# 4channelsRelaySwitchv2.net
KiCad netlist of a schematic drawn in EAGLE
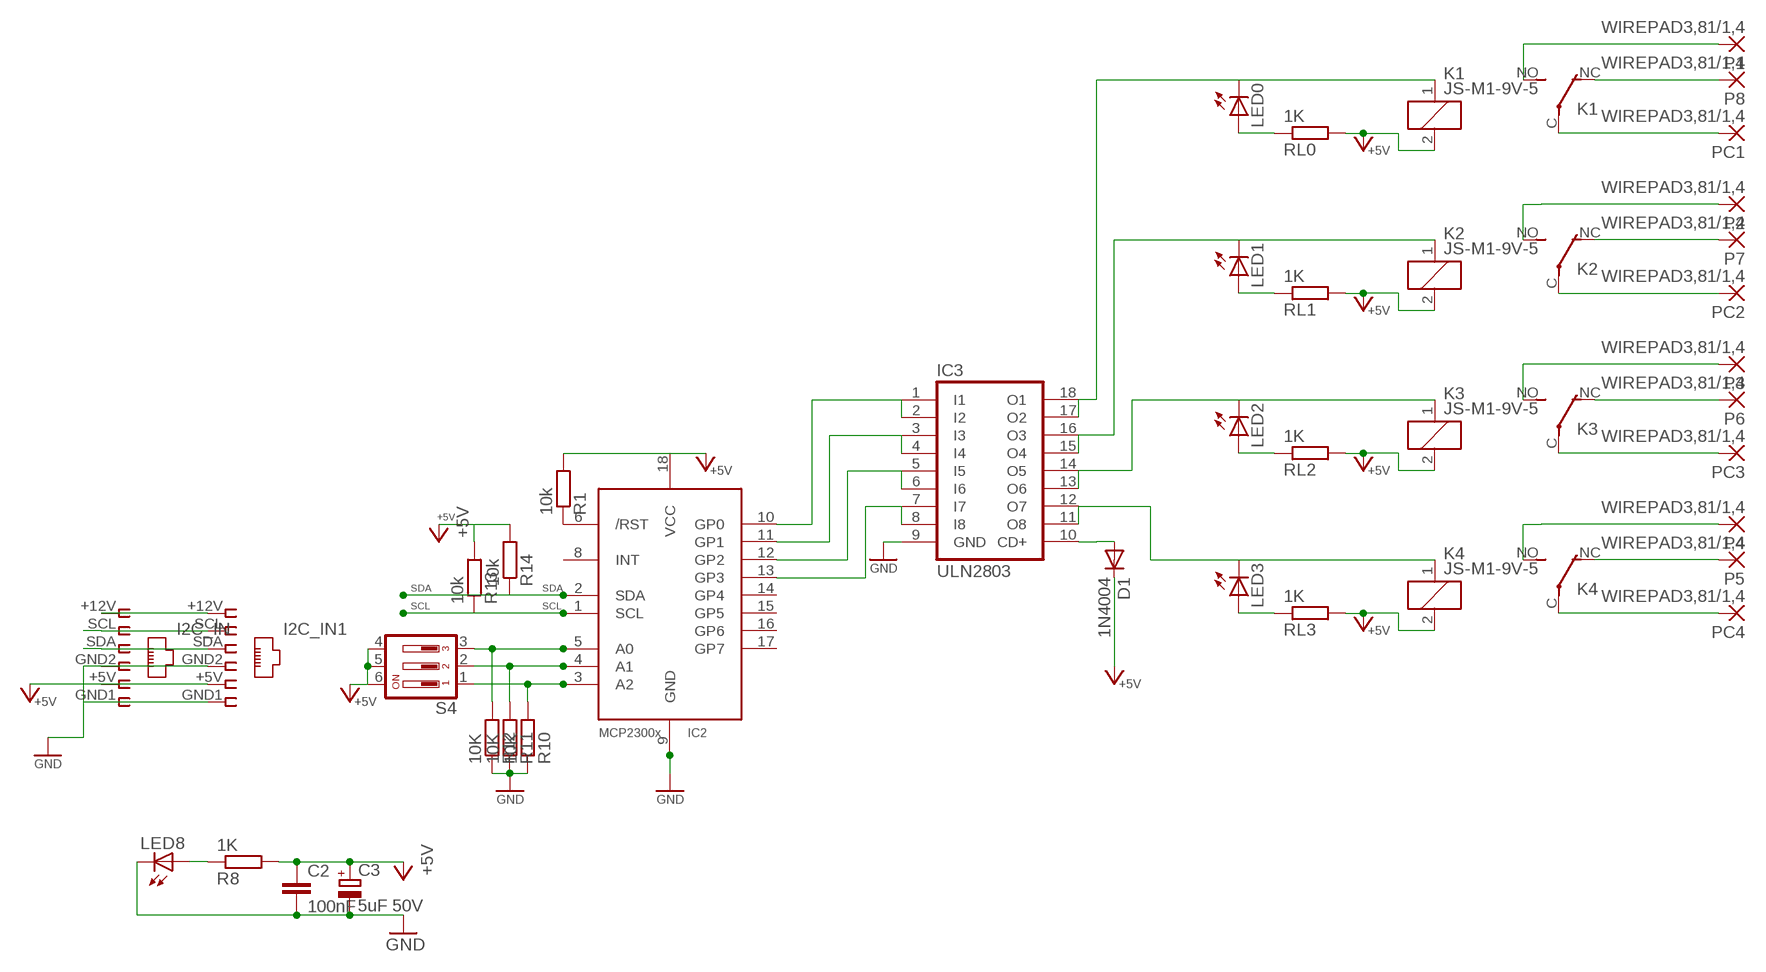
[diagram p0: schematic, sheet 1]

(export (version "E")
  (design (tool "Eeschema 10.0.6"))
  (components
    (comp (ref "C2")
      (value "100nF")
      (footprint "eagle-import:C1206")
      (libsource (lib "eagle-import") (part "C-EUC1206"))
    )
    (comp (ref "C3")
      (value "5uF 50V")
      (footprint "eagle-import:E3,5-8")
      (libsource (lib "eagle-import") (part "CPOL-EUE3.5-8"))
    )
    (comp (ref "D1")
      (value "1N4004")
      (footprint "eagle-import:DO41-10")
      (libsource (lib "eagle-import") (part "1N4004"))
    )
    (comp (ref "I2C_IN")
      (value "I2C 1")
      (footprint "eagle-import:RJ12-STRAIGHT-I2C")
      (libsource (lib "eagle-import") (part "RJ12STRAIGHT-I2C"))
    )
    (comp (ref "I2C_IN1")
      (value "I2C 2")
      (footprint "eagle-import:RJ12-STRAIGHT-I2C")
      (libsource (lib "eagle-import") (part "RJ12STRAIGHT-I2C"))
    )
    (comp (ref "IC2")
      (value "MCP2300X/P")
      (footprint "eagle-import:DIL18")
      (libsource (lib "eagle-import") (part "MCP2300X/P"))
    )
    (comp (ref "IC3")
      (value "ULN2803")
      (footprint "eagle-import:DIL18")
      (libsource (lib "eagle-import") (part "ULN2803A"))
    )
    (comp (ref "K1")
      (value "JS-M1-9V-5")
      (footprint "eagle-import:JS-M")
      (libsource (lib "eagle-import") (part "JS-M1-9V-5"))
    )
    (comp (ref "K2")
      (value "JS-M1-9V-5")
      (footprint "eagle-import:JS-M")
      (libsource (lib "eagle-import") (part "JS-M1-9V-5"))
    )
    (comp (ref "K3")
      (value "JS-M1-9V-5")
      (footprint "eagle-import:JS-M")
      (libsource (lib "eagle-import") (part "JS-M1-9V-5"))
    )
    (comp (ref "K4")
      (value "JS-M1-9V-5")
      (footprint "eagle-import:JS-M")
      (libsource (lib "eagle-import") (part "JS-M1-9V-5"))
    )
    (comp (ref "LED0")
      (value "LED3MM")
      (footprint "eagle-import:LED3MM")
      (libsource (lib "eagle-import") (part "LED3MM"))
    )
    (comp (ref "LED1")
      (value "LED3MM")
      (footprint "eagle-import:LED3MM")
      (libsource (lib "eagle-import") (part "LED3MM"))
    )
    (comp (ref "LED2")
      (value "LED3MM")
      (footprint "eagle-import:LED3MM")
      (libsource (lib "eagle-import") (part "LED3MM"))
    )
    (comp (ref "LED3")
      (value "LED3MM")
      (footprint "eagle-import:LED3MM")
      (libsource (lib "eagle-import") (part "LED3MM"))
    )
    (comp (ref "LED8")
      (value "LED3MM")
      (footprint "eagle-import:LED3MM")
      (libsource (lib "eagle-import") (part "LED3MM"))
    )
    (comp (ref "P1")
      (value "WIREPAD3,81/1,4")
      (footprint "eagle-import:3,81_1,4")
      (libsource (lib "eagle-import") (part "WIREPAD3,81/1,4"))
    )
    (comp (ref "P2")
      (value "WIREPAD3,81/1,4")
      (footprint "eagle-import:3,81_1,4")
      (libsource (lib "eagle-import") (part "WIREPAD3,81/1,4"))
    )
    (comp (ref "P3")
      (value "WIREPAD3,81/1,4")
      (footprint "eagle-import:3,81_1,4")
      (libsource (lib "eagle-import") (part "WIREPAD3,81/1,4"))
    )
    (comp (ref "P4")
      (value "WIREPAD3,81/1,4")
      (footprint "eagle-import:3,81_1,4")
      (libsource (lib "eagle-import") (part "WIREPAD3,81/1,4"))
    )
    (comp (ref "P5")
      (value "WIREPAD3,81/1,4")
      (footprint "eagle-import:3,81_1,4")
      (libsource (lib "eagle-import") (part "WIREPAD3,81/1,4"))
    )
    (comp (ref "P6")
      (value "WIREPAD3,81/1,4")
      (footprint "eagle-import:3,81_1,4")
      (libsource (lib "eagle-import") (part "WIREPAD3,81/1,4"))
    )
    (comp (ref "P7")
      (value "WIREPAD3,81/1,4")
      (footprint "eagle-import:3,81_1,4")
      (libsource (lib "eagle-import") (part "WIREPAD3,81/1,4"))
    )
    (comp (ref "P8")
      (value "WIREPAD3,81/1,4")
      (footprint "eagle-import:3,81_1,4")
      (libsource (lib "eagle-import") (part "WIREPAD3,81/1,4"))
    )
    (comp (ref "PC1")
      (value "WIREPAD3,81/1,4")
      (footprint "eagle-import:3,81_1,4")
      (libsource (lib "eagle-import") (part "WIREPAD3,81/1,4"))
    )
    (comp (ref "PC2")
      (value "WIREPAD3,81/1,4")
      (footprint "eagle-import:3,81_1,4")
      (libsource (lib "eagle-import") (part "WIREPAD3,81/1,4"))
    )
    (comp (ref "PC3")
      (value "WIREPAD3,81/1,4")
      (footprint "eagle-import:3,81_1,4")
      (libsource (lib "eagle-import") (part "WIREPAD3,81/1,4"))
    )
    (comp (ref "PC4")
      (value "WIREPAD3,81/1,4")
      (footprint "eagle-import:3,81_1,4")
      (libsource (lib "eagle-import") (part "WIREPAD3,81/1,4"))
    )
    (comp (ref "R1")
      (value "10k")
      (footprint "eagle-import:M1206")
      (libsource (lib "eagle-import") (part "R-EU_M1206"))
    )
    (comp (ref "R8")
      (value "1K")
      (footprint "eagle-import:M1206")
      (libsource (lib "eagle-import") (part "R-EU_M1206"))
    )
    (comp (ref "R10")
      (value "10K")
      (footprint "eagle-import:M1206")
      (libsource (lib "eagle-import") (part "R-EU_M1206"))
    )
    (comp (ref "R11")
      (value "10K")
      (footprint "eagle-import:M1206")
      (libsource (lib "eagle-import") (part "R-EU_M1206"))
    )
    (comp (ref "R12")
      (value "10K")
      (footprint "eagle-import:M1206")
      (libsource (lib "eagle-import") (part "R-EU_M1206"))
    )
    (comp (ref "R13")
      (value "10k")
      (footprint "eagle-import:M1206")
      (libsource (lib "eagle-import") (part "R-EU_M1206"))
    )
    (comp (ref "R14")
      (value "10k")
      (footprint "eagle-import:M1206")
      (libsource (lib "eagle-import") (part "R-EU_M1206"))
    )
    (comp (ref "RL0")
      (value "1K")
      (footprint "eagle-import:M1206")
      (libsource (lib "eagle-import") (part "R-EU_M1206"))
    )
    (comp (ref "RL1")
      (value "1K")
      (footprint "eagle-import:M1206")
      (libsource (lib "eagle-import") (part "R-EU_M1206"))
    )
    (comp (ref "RL2")
      (value "1K")
      (footprint "eagle-import:M1206")
      (libsource (lib "eagle-import") (part "R-EU_M1206"))
    )
    (comp (ref "RL3")
      (value "1K")
      (footprint "eagle-import:M1206")
      (libsource (lib "eagle-import") (part "R-EU_M1206"))
    )
    (comp (ref "S4")
      (value "DIP03YL")
      (footprint "eagle-import:DIP03YL")
      (libsource (lib "eagle-import") (part "DIP03YL"))
    )
  )
  (nets
    (net (code "1") (name "+5V") (class "Default")
      (node (ref "C2") (pin "1") (pinfunction "1_1") (pintype "passive"))
      (node (ref "C3") (pin "+") (pinfunction "+_+") (pintype "passive"))
      (node (ref "D1") (pin "C") (pinfunction "C_C") (pintype "passive"))
      (node (ref "I2C_IN") (pin "+5V") (pinfunction "5_+5V") (pintype "power_in"))
      (node (ref "I2C_IN1") (pin "+5V") (pinfunction "5_+5V") (pintype "power_in"))
      (node (ref "IC2") (pin "18") (pinfunction "VCC_18") (pintype "power_in"))
      (node (ref "K1") (pin "2") (pinfunction "2_2") (pintype "passive"))
      (node (ref "K2") (pin "2") (pinfunction "2_2") (pintype "passive"))
      (node (ref "K3") (pin "2") (pinfunction "2_2") (pintype "passive"))
      (node (ref "K4") (pin "2") (pinfunction "2_2") (pintype "passive"))
      (node (ref "R1") (pin "2") (pinfunction "2_2") (pintype "passive"))
      (node (ref "R13") (pin "2") (pinfunction "2_2") (pintype "passive"))
      (node (ref "R14") (pin "2") (pinfunction "2_2") (pintype "passive"))
      (node (ref "R8") (pin "2") (pinfunction "2_2") (pintype "passive"))
      (node (ref "RL0") (pin "2") (pinfunction "2_2") (pintype "passive"))
      (node (ref "RL1") (pin "2") (pinfunction "2_2") (pintype "passive"))
      (node (ref "RL2") (pin "2") (pinfunction "2_2") (pintype "passive"))
      (node (ref "RL3") (pin "2") (pinfunction "2_2") (pintype "passive"))
      (node (ref "S4") (pin "4") (pinfunction "4_4") (pintype "passive"))
      (node (ref "S4") (pin "5") (pinfunction "5_5") (pintype "passive"))
      (node (ref "S4") (pin "6") (pinfunction "6_6") (pintype "passive"))
    )
    (net (code "2") (name "/SCL") (class "Default")
      (node (ref "I2C_IN") (pin "SCL") (pinfunction "2_SCL") (pintype "bidirectional"))
      (node (ref "I2C_IN1") (pin "SCL") (pinfunction "2_SCL") (pintype "bidirectional"))
      (node (ref "IC2") (pin "1") (pinfunction "SCL_1") (pintype "bidirectional"))
      (node (ref "R13") (pin "1") (pinfunction "1_1") (pintype "passive"))
    )
    (net (code "3") (name "/SDA") (class "Default")
      (node (ref "I2C_IN") (pin "SDA") (pinfunction "3_SDA") (pintype "bidirectional"))
      (node (ref "I2C_IN1") (pin "SDA") (pinfunction "3_SDA") (pintype "bidirectional"))
      (node (ref "IC2") (pin "2") (pinfunction "SDA_2") (pintype "bidirectional"))
      (node (ref "R14") (pin "1") (pinfunction "1_1") (pintype "passive"))
    )
    (net (code "4") (name "GND") (class "Default")
      (node (ref "C2") (pin "2") (pinfunction "2_2") (pintype "passive"))
      (node (ref "C3") (pin "-") (pinfunction "-_-") (pintype "passive"))
      (node (ref "I2C_IN") (pin "GND1") (pinfunction "6_GND1") (pintype "power_in"))
      (node (ref "I2C_IN") (pin "GND2") (pinfunction "4_GND2") (pintype "power_in"))
      (node (ref "I2C_IN1") (pin "GND1") (pinfunction "6_GND1") (pintype "power_in"))
      (node (ref "I2C_IN1") (pin "GND2") (pinfunction "4_GND2") (pintype "power_in"))
      (node (ref "IC2") (pin "9") (pinfunction "GND_9") (pintype "power_in"))
      (node (ref "IC3") (pin "9") (pinfunction "GND_9") (pintype "power_in"))
      (node (ref "LED8") (pin "K") (pinfunction "C_K") (pintype "passive"))
      (node (ref "R10") (pin "1") (pinfunction "1_1") (pintype "passive"))
      (node (ref "R11") (pin "1") (pinfunction "1_1") (pintype "passive"))
      (node (ref "R12") (pin "1") (pinfunction "1_1") (pintype "passive"))
    )
    (net (code "5") (name "Net-(I2C_IN-1)") (class "Default")
      (node (ref "I2C_IN") (pin "+12V") (pinfunction "1_+12V") (pintype "power_in"))
      (node (ref "I2C_IN1") (pin "+12V") (pinfunction "1_+12V") (pintype "power_in"))
    )
    (net (code "6") (name "Net-(IC2-A0)") (class "Default")
      (node (ref "IC2") (pin "5") (pinfunction "A0_5") (pintype "input"))
      (node (ref "R12") (pin "2") (pinfunction "2_2") (pintype "passive"))
      (node (ref "S4") (pin "3") (pinfunction "3_3") (pintype "passive"))
    )
    (net (code "7") (name "Net-(IC2-A1)") (class "Default")
      (node (ref "IC2") (pin "4") (pinfunction "A1_4") (pintype "input"))
      (node (ref "R11") (pin "2") (pinfunction "2_2") (pintype "passive"))
      (node (ref "S4") (pin "2") (pinfunction "2_2") (pintype "passive"))
    )
    (net (code "8") (name "Net-(IC2-A2)") (class "Default")
      (node (ref "IC2") (pin "3") (pinfunction "A2_3") (pintype "input"))
      (node (ref "R10") (pin "2") (pinfunction "2_2") (pintype "passive"))
      (node (ref "S4") (pin "1") (pinfunction "1_1") (pintype "passive"))
    )
    (net (code "9") (name "Net-(IC2-GP0)") (class "Default")
      (node (ref "IC2") (pin "10") (pinfunction "GP0_10") (pintype "bidirectional"))
      (node (ref "IC3") (pin "1") (pinfunction "I1_1") (pintype "input"))
      (node (ref "IC3") (pin "2") (pinfunction "I2_2") (pintype "input"))
    )
    (net (code "10") (name "Net-(IC2-GP1)") (class "Default")
      (node (ref "IC2") (pin "11") (pinfunction "GP1_11") (pintype "bidirectional"))
      (node (ref "IC3") (pin "3") (pinfunction "I3_3") (pintype "input"))
      (node (ref "IC3") (pin "4") (pinfunction "I4_4") (pintype "input"))
    )
    (net (code "11") (name "Net-(IC2-GP2)") (class "Default")
      (node (ref "IC2") (pin "12") (pinfunction "GP2_12") (pintype "bidirectional"))
      (node (ref "IC3") (pin "5") (pinfunction "I5_5") (pintype "input"))
      (node (ref "IC3") (pin "6") (pinfunction "I6_6") (pintype "input"))
    )
    (net (code "12") (name "Net-(IC2-GP3)") (class "Default")
      (node (ref "IC2") (pin "13") (pinfunction "GP3_13") (pintype "bidirectional"))
      (node (ref "IC3") (pin "7") (pinfunction "I7_7") (pintype "input"))
      (node (ref "IC3") (pin "8") (pinfunction "I8_8") (pintype "input"))
    )
    (net (code "13") (name "Net-(IC2-{slash}RST)") (class "Default")
      (node (ref "IC2") (pin "6") (pinfunction "/RST_6") (pintype "input"))
      (node (ref "R1") (pin "1") (pinfunction "1_1") (pintype "passive"))
    )
    (net (code "14") (name "Net-(IC3-CD+)") (class "Default")
      (node (ref "D1") (pin "A") (pinfunction "A_A") (pintype "passive"))
      (node (ref "IC3") (pin "10") (pinfunction "CD+_10") (pintype "passive"))
    )
    (net (code "15") (name "Net-(IC3-O1)") (class "Default")
      (node (ref "IC3") (pin "17") (pinfunction "O2_17") (pintype "open_collector"))
      (node (ref "IC3") (pin "18") (pinfunction "O1_18") (pintype "open_collector"))
      (node (ref "K1") (pin "1") (pinfunction "1_1") (pintype "passive"))
      (node (ref "LED0") (pin "K") (pinfunction "C_K") (pintype "passive"))
    )
    (net (code "16") (name "Net-(IC3-O3)") (class "Default")
      (node (ref "IC3") (pin "15") (pinfunction "O4_15") (pintype "open_collector"))
      (node (ref "IC3") (pin "16") (pinfunction "O3_16") (pintype "open_collector"))
      (node (ref "K2") (pin "1") (pinfunction "1_1") (pintype "passive"))
      (node (ref "LED1") (pin "K") (pinfunction "C_K") (pintype "passive"))
    )
    (net (code "17") (name "Net-(IC3-O5)") (class "Default")
      (node (ref "IC3") (pin "13") (pinfunction "O6_13") (pintype "open_collector"))
      (node (ref "IC3") (pin "14") (pinfunction "O5_14") (pintype "open_collector"))
      (node (ref "K3") (pin "1") (pinfunction "1_1") (pintype "passive"))
      (node (ref "LED2") (pin "K") (pinfunction "C_K") (pintype "passive"))
    )
    (net (code "18") (name "Net-(IC3-O7)") (class "Default")
      (node (ref "IC3") (pin "11") (pinfunction "O8_11") (pintype "open_collector"))
      (node (ref "IC3") (pin "12") (pinfunction "O7_12") (pintype "open_collector"))
      (node (ref "K4") (pin "1") (pinfunction "1_1") (pintype "passive"))
      (node (ref "LED3") (pin "K") (pinfunction "C_K") (pintype "passive"))
    )
    (net (code "19") (name "Net-(K1B-O)") (class "Default")
      (node (ref "K1") (pin "NC") (pinfunction "O_NC") (pintype "passive"))
      (node (ref "P8") (pin "1") (pinfunction "P_1") (pintype "passive"))
    )
    (net (code "20") (name "Net-(K1B-P)") (class "Default")
      (node (ref "K1") (pin "C") (pinfunction "P_C") (pintype "passive"))
      (node (ref "PC1") (pin "1") (pinfunction "P_1") (pintype "passive"))
    )
    (net (code "21") (name "Net-(K1B-S)") (class "Default")
      (node (ref "K1") (pin "NO") (pinfunction "S_NO") (pintype "passive"))
      (node (ref "P1") (pin "1") (pinfunction "P_1") (pintype "passive"))
    )
    (net (code "22") (name "Net-(K2B-O)") (class "Default")
      (node (ref "K2") (pin "NC") (pinfunction "O_NC") (pintype "passive"))
      (node (ref "P7") (pin "1") (pinfunction "P_1") (pintype "passive"))
    )
    (net (code "23") (name "Net-(K2B-P)") (class "Default")
      (node (ref "K2") (pin "C") (pinfunction "P_C") (pintype "passive"))
      (node (ref "PC2") (pin "1") (pinfunction "P_1") (pintype "passive"))
    )
    (net (code "24") (name "Net-(K2B-S)") (class "Default")
      (node (ref "K2") (pin "NO") (pinfunction "S_NO") (pintype "passive"))
      (node (ref "P2") (pin "1") (pinfunction "P_1") (pintype "passive"))
    )
    (net (code "25") (name "Net-(K3B-O)") (class "Default")
      (node (ref "K3") (pin "NC") (pinfunction "O_NC") (pintype "passive"))
      (node (ref "P6") (pin "1") (pinfunction "P_1") (pintype "passive"))
    )
    (net (code "26") (name "Net-(K3B-P)") (class "Default")
      (node (ref "K3") (pin "C") (pinfunction "P_C") (pintype "passive"))
      (node (ref "PC3") (pin "1") (pinfunction "P_1") (pintype "passive"))
    )
    (net (code "27") (name "Net-(K3B-S)") (class "Default")
      (node (ref "K3") (pin "NO") (pinfunction "S_NO") (pintype "passive"))
      (node (ref "P3") (pin "1") (pinfunction "P_1") (pintype "passive"))
    )
    (net (code "28") (name "Net-(K4B-O)") (class "Default")
      (node (ref "K4") (pin "NC") (pinfunction "O_NC") (pintype "passive"))
      (node (ref "P5") (pin "1") (pinfunction "P_1") (pintype "passive"))
    )
    (net (code "29") (name "Net-(K4B-P)") (class "Default")
      (node (ref "K4") (pin "C") (pinfunction "P_C") (pintype "passive"))
      (node (ref "PC4") (pin "1") (pinfunction "P_1") (pintype "passive"))
    )
    (net (code "30") (name "Net-(K4B-S)") (class "Default")
      (node (ref "K4") (pin "NO") (pinfunction "S_NO") (pintype "passive"))
      (node (ref "P4") (pin "1") (pinfunction "P_1") (pintype "passive"))
    )
    (net (code "31") (name "Net-(LED0-PadA)") (class "Default")
      (node (ref "LED0") (pin "A") (pinfunction "A_A") (pintype "passive"))
      (node (ref "RL0") (pin "1") (pinfunction "1_1") (pintype "passive"))
    )
    (net (code "32") (name "Net-(LED1-PadA)") (class "Default")
      (node (ref "LED1") (pin "A") (pinfunction "A_A") (pintype "passive"))
      (node (ref "RL1") (pin "1") (pinfunction "1_1") (pintype "passive"))
    )
    (net (code "33") (name "Net-(LED2-PadA)") (class "Default")
      (node (ref "LED2") (pin "A") (pinfunction "A_A") (pintype "passive"))
      (node (ref "RL2") (pin "1") (pinfunction "1_1") (pintype "passive"))
    )
    (net (code "34") (name "Net-(LED3-PadA)") (class "Default")
      (node (ref "LED3") (pin "A") (pinfunction "A_A") (pintype "passive"))
      (node (ref "RL3") (pin "1") (pinfunction "1_1") (pintype "passive"))
    )
    (net (code "35") (name "Net-(LED8-PadA)") (class "Default")
      (node (ref "LED8") (pin "A") (pinfunction "A_A") (pintype "passive"))
      (node (ref "R8") (pin "1") (pinfunction "1_1") (pintype "passive"))
    )
    (net (code "36") (name "unconnected-(IC2-GP4-Pad14)") (class "Default")
      (node (ref "IC2") (pin "14") (pinfunction "GP4_14") (pintype "bidirectional"))
    )
    (net (code "37") (name "unconnected-(IC2-GP5-Pad15)") (class "Default")
      (node (ref "IC2") (pin "15") (pinfunction "GP5_15") (pintype "bidirectional"))
    )
    (net (code "38") (name "unconnected-(IC2-GP6-Pad16)") (class "Default")
      (node (ref "IC2") (pin "16") (pinfunction "GP6_16") (pintype "bidirectional"))
    )
    (net (code "39") (name "unconnected-(IC2-GP7-Pad17)") (class "Default")
      (node (ref "IC2") (pin "17") (pinfunction "GP7_17") (pintype "bidirectional"))
    )
    (net (code "40") (name "unconnected-(IC2-INT-Pad8)") (class "Default")
      (node (ref "IC2") (pin "8") (pinfunction "INT_8") (pintype "output"))
    )
  )
)
